# 7segement4digits1badidea-shield-mk-4.net
KiCad netlist of a schematic drawn in EAGLE
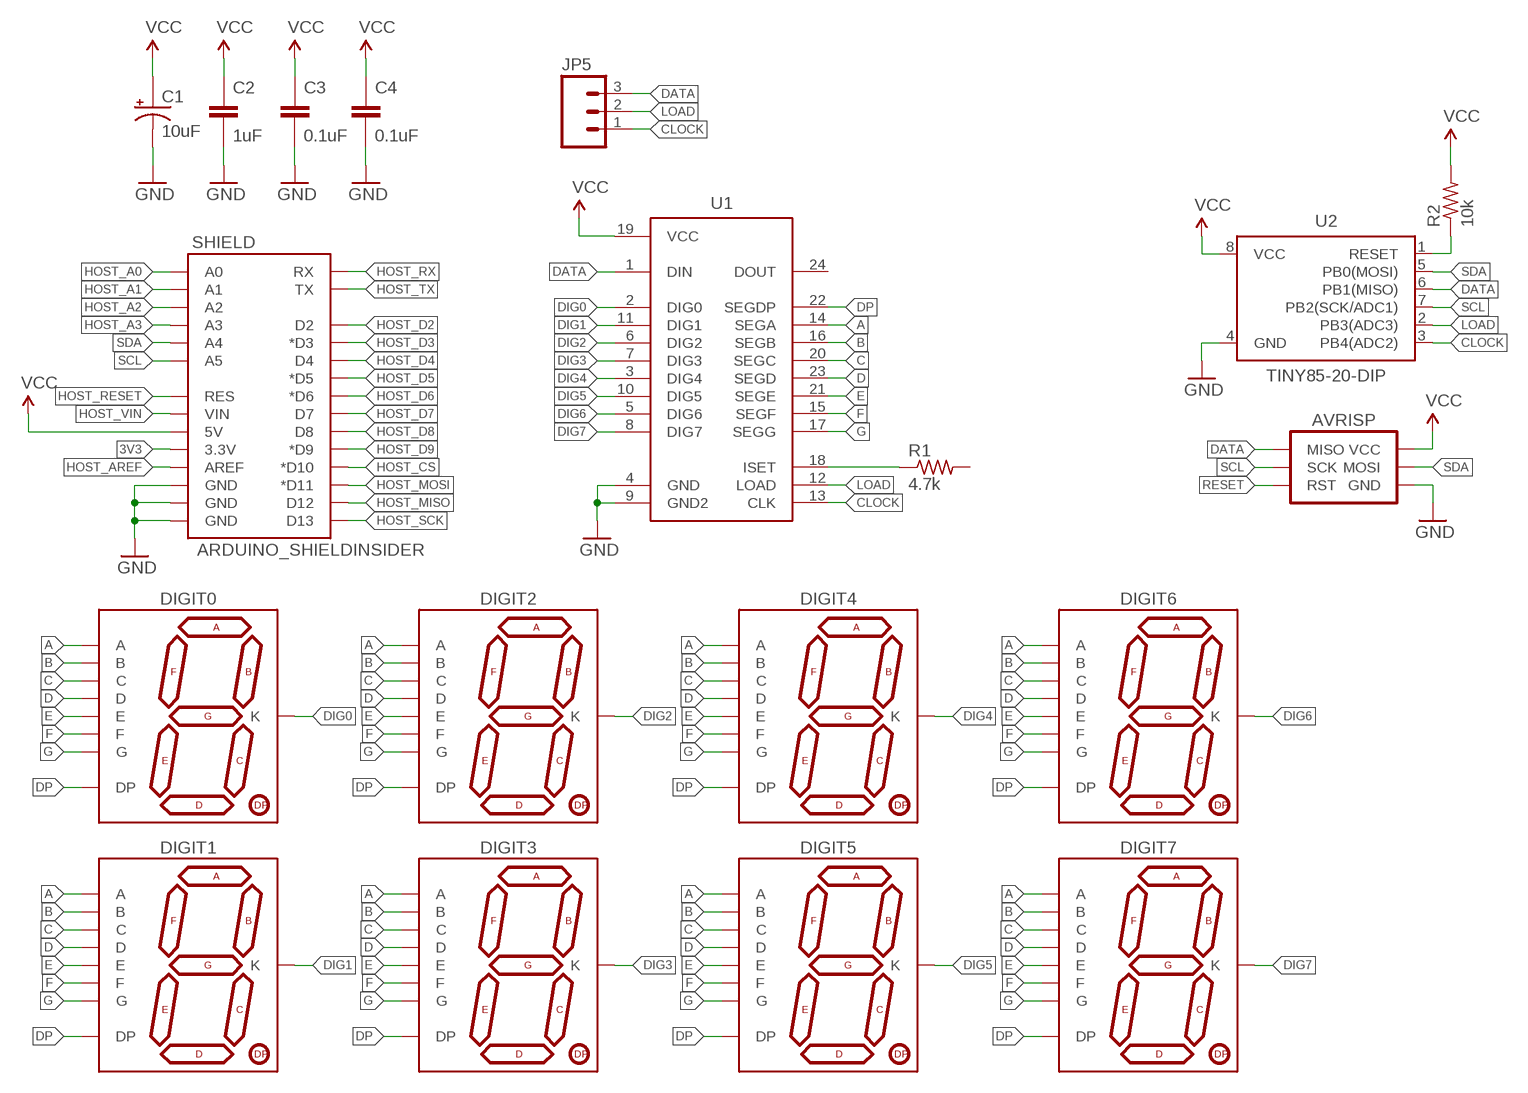
[diagram p0: schematic, sheet 1]

(export (version "E")
  (design (tool "Eeschema 10.0.6"))
  (components
    (comp (ref "AVRISP")
      (value "AVR_SPI_PRG_6PTH")
      (footprint "eagle-import:2X3")
      (libsource (lib "eagle-import") (part "AVR_SPI_PRG_6PTH"))
    )
    (comp (ref "C1")
      (value "10uF")
      (footprint "eagle-import:E2,5-5")
      (libsource (lib "eagle-import") (part "CAPACITOR-POLARIZEDE2.5-5"))
    )
    (comp (ref "C2")
      (value "1uF")
      (footprint "eagle-import:C025-024X044")
      (libsource (lib "eagle-import") (part "CAPACITOR-CERAMIC025-024X044"))
    )
    (comp (ref "C3")
      (value "0.1uF")
      (footprint "eagle-import:C025-024X044")
      (libsource (lib "eagle-import") (part "CAPACITOR-CERAMIC025-024X044"))
    )
    (comp (ref "C4")
      (value "0.1uF")
      (footprint "eagle-import:C025-024X044")
      (libsource (lib "eagle-import") (part "CAPACITOR-CERAMIC025-024X044"))
    )
    (comp (ref "DIGIT0")
      (value "7SEG_1DIGPTH-10MM")
      (footprint "eagle-import:7SEG_1DIG_10MM")
      (libsource (lib "eagle-import") (part "7SEG_1DIGPTH-10MM"))
    )
    (comp (ref "DIGIT1")
      (value "7SEG_1DIGPTH-10MM")
      (footprint "eagle-import:7SEG_1DIG_10MM")
      (libsource (lib "eagle-import") (part "7SEG_1DIGPTH-10MM"))
    )
    (comp (ref "DIGIT2")
      (value "7SEG_1DIGPTH-10MM")
      (footprint "eagle-import:7SEG_1DIG_10MM")
      (libsource (lib "eagle-import") (part "7SEG_1DIGPTH-10MM"))
    )
    (comp (ref "DIGIT3")
      (value "7SEG_1DIGPTH-10MM")
      (footprint "eagle-import:7SEG_1DIG_10MM")
      (libsource (lib "eagle-import") (part "7SEG_1DIGPTH-10MM"))
    )
    (comp (ref "DIGIT4")
      (value "7SEG_1DIGPTH-10MM")
      (footprint "eagle-import:7SEG_1DIG_10MM")
      (libsource (lib "eagle-import") (part "7SEG_1DIGPTH-10MM"))
    )
    (comp (ref "DIGIT5")
      (value "7SEG_1DIGPTH-10MM")
      (footprint "eagle-import:7SEG_1DIG_10MM")
      (libsource (lib "eagle-import") (part "7SEG_1DIGPTH-10MM"))
    )
    (comp (ref "DIGIT6")
      (value "7SEG_1DIGPTH-10MM")
      (footprint "eagle-import:7SEG_1DIG_10MM")
      (libsource (lib "eagle-import") (part "7SEG_1DIGPTH-10MM"))
    )
    (comp (ref "DIGIT7")
      (value "7SEG_1DIGPTH-10MM")
      (footprint "eagle-import:7SEG_1DIG_10MM")
      (libsource (lib "eagle-import") (part "7SEG_1DIGPTH-10MM"))
    )
    (comp (ref "JP5")
      (value "M03PTH")
      (footprint "eagle-import:1X03")
      (libsource (lib "eagle-import") (part "M03PTH"))
    )
    (comp (ref "R1")
      (value "4.7k")
      (footprint "eagle-import:RESISTOR-AXIAL-PTH-7.68MM")
      (libsource (lib "eagle-import") (part "RESISTORPTH-AXIAL-7.68MM"))
    )
    (comp (ref "R2")
      (value "10k")
      (footprint "eagle-import:RESISTOR-AXIAL-PTH-7.68MM")
      (libsource (lib "eagle-import") (part "RESISTORPTH-AXIAL-7.68MM"))
    )
    (comp (ref "SHIELD")
      (value "ARDUINO_SHIELDINSIDER")
      (footprint "eagle-import:ARDUINO_SHIELD_NOOUTLINE_INSIDE")
      (libsource (lib "eagle-import") (part "ARDUINO_SHIELDINSIDER"))
    )
    (comp (ref "U1")
      (value "MAX7219DIP")
      (footprint "eagle-import:DIL24")
      (libsource (lib "eagle-import") (part "MAX7219DIP"))
    )
    (comp (ref "U2")
      (value "TINY85-20-DIP")
      (footprint "eagle-import:DIP08")
      (libsource (lib "eagle-import") (part "ATTINY45TINY85-20-DIP"))
    )
  )
  (nets
    (net (code "1") (name "3V3") (class "Default")
      (node (ref "SHIELD") (pin "3.3V") (pinfunction "3.3V_3.3V") (pintype "bidirectional"))
    )
    (net (code "2") (name "A") (class "Default")
      (node (ref "DIGIT0") (pin "10") (pinfunction "A_10") (pintype "bidirectional"))
      (node (ref "DIGIT1") (pin "10") (pinfunction "A_10") (pintype "bidirectional"))
      (node (ref "DIGIT2") (pin "10") (pinfunction "A_10") (pintype "bidirectional"))
      (node (ref "DIGIT3") (pin "10") (pinfunction "A_10") (pintype "bidirectional"))
      (node (ref "DIGIT4") (pin "10") (pinfunction "A_10") (pintype "bidirectional"))
      (node (ref "DIGIT5") (pin "10") (pinfunction "A_10") (pintype "bidirectional"))
      (node (ref "DIGIT6") (pin "10") (pinfunction "A_10") (pintype "bidirectional"))
      (node (ref "DIGIT7") (pin "10") (pinfunction "A_10") (pintype "bidirectional"))
      (node (ref "U1") (pin "14") (pinfunction "SEGA_14") (pintype "bidirectional"))
    )
    (net (code "3") (name "B") (class "Default")
      (node (ref "DIGIT0") (pin "9") (pinfunction "B_9") (pintype "bidirectional"))
      (node (ref "DIGIT1") (pin "9") (pinfunction "B_9") (pintype "bidirectional"))
      (node (ref "DIGIT2") (pin "9") (pinfunction "B_9") (pintype "bidirectional"))
      (node (ref "DIGIT3") (pin "9") (pinfunction "B_9") (pintype "bidirectional"))
      (node (ref "DIGIT4") (pin "9") (pinfunction "B_9") (pintype "bidirectional"))
      (node (ref "DIGIT5") (pin "9") (pinfunction "B_9") (pintype "bidirectional"))
      (node (ref "DIGIT6") (pin "9") (pinfunction "B_9") (pintype "bidirectional"))
      (node (ref "DIGIT7") (pin "9") (pinfunction "B_9") (pintype "bidirectional"))
      (node (ref "U1") (pin "16") (pinfunction "SEGB_16") (pintype "bidirectional"))
    )
    (net (code "4") (name "C") (class "Default")
      (node (ref "DIGIT0") (pin "8") (pinfunction "C_8") (pintype "bidirectional"))
      (node (ref "DIGIT1") (pin "8") (pinfunction "C_8") (pintype "bidirectional"))
      (node (ref "DIGIT2") (pin "8") (pinfunction "C_8") (pintype "bidirectional"))
      (node (ref "DIGIT3") (pin "8") (pinfunction "C_8") (pintype "bidirectional"))
      (node (ref "DIGIT4") (pin "8") (pinfunction "C_8") (pintype "bidirectional"))
      (node (ref "DIGIT5") (pin "8") (pinfunction "C_8") (pintype "bidirectional"))
      (node (ref "DIGIT6") (pin "8") (pinfunction "C_8") (pintype "bidirectional"))
      (node (ref "DIGIT7") (pin "8") (pinfunction "C_8") (pintype "bidirectional"))
      (node (ref "U1") (pin "20") (pinfunction "SEGC_20") (pintype "bidirectional"))
    )
    (net (code "5") (name "CLOCK") (class "Default")
      (node (ref "JP5") (pin "1") (pinfunction "1_1") (pintype "passive"))
      (node (ref "U1") (pin "13") (pinfunction "CLK_13") (pintype "bidirectional"))
      (node (ref "U2") (pin "3") (pinfunction "PB4(ADC2)_3") (pintype "bidirectional"))
    )
    (net (code "6") (name "D") (class "Default")
      (node (ref "DIGIT0") (pin "5") (pinfunction "D_5") (pintype "bidirectional"))
      (node (ref "DIGIT1") (pin "5") (pinfunction "D_5") (pintype "bidirectional"))
      (node (ref "DIGIT2") (pin "5") (pinfunction "D_5") (pintype "bidirectional"))
      (node (ref "DIGIT3") (pin "5") (pinfunction "D_5") (pintype "bidirectional"))
      (node (ref "DIGIT4") (pin "5") (pinfunction "D_5") (pintype "bidirectional"))
      (node (ref "DIGIT5") (pin "5") (pinfunction "D_5") (pintype "bidirectional"))
      (node (ref "DIGIT6") (pin "5") (pinfunction "D_5") (pintype "bidirectional"))
      (node (ref "DIGIT7") (pin "5") (pinfunction "D_5") (pintype "bidirectional"))
      (node (ref "U1") (pin "23") (pinfunction "SEGD_23") (pintype "bidirectional"))
    )
    (net (code "7") (name "DATA") (class "Default")
      (node (ref "AVRISP") (pin "1") (pinfunction "MISO_1") (pintype "passive"))
      (node (ref "JP5") (pin "3") (pinfunction "3_3") (pintype "passive"))
      (node (ref "U1") (pin "1") (pinfunction "DIN_1") (pintype "bidirectional"))
      (node (ref "U2") (pin "6") (pinfunction "PB1(MISO)_6") (pintype "bidirectional"))
    )
    (net (code "8") (name "DIG0") (class "Default")
      (node (ref "DIGIT0") (pin "1") (pinfunction "K_1") (pintype "bidirectional"))
      (node (ref "DIGIT0") (pin "6") (pinfunction "K_6") (pintype "bidirectional"))
      (node (ref "U1") (pin "2") (pinfunction "DIG0_2") (pintype "bidirectional"))
    )
    (net (code "9") (name "DIG1") (class "Default")
      (node (ref "DIGIT1") (pin "1") (pinfunction "K_1") (pintype "bidirectional"))
      (node (ref "DIGIT1") (pin "6") (pinfunction "K_6") (pintype "bidirectional"))
      (node (ref "U1") (pin "11") (pinfunction "DIG1_11") (pintype "bidirectional"))
    )
    (net (code "10") (name "DIG2") (class "Default")
      (node (ref "DIGIT2") (pin "1") (pinfunction "K_1") (pintype "bidirectional"))
      (node (ref "DIGIT2") (pin "6") (pinfunction "K_6") (pintype "bidirectional"))
      (node (ref "U1") (pin "6") (pinfunction "DIG2_6") (pintype "bidirectional"))
    )
    (net (code "11") (name "DIG3") (class "Default")
      (node (ref "DIGIT3") (pin "1") (pinfunction "K_1") (pintype "bidirectional"))
      (node (ref "DIGIT3") (pin "6") (pinfunction "K_6") (pintype "bidirectional"))
      (node (ref "U1") (pin "7") (pinfunction "DIG3_7") (pintype "bidirectional"))
    )
    (net (code "12") (name "DIG4") (class "Default")
      (node (ref "DIGIT4") (pin "1") (pinfunction "K_1") (pintype "bidirectional"))
      (node (ref "DIGIT4") (pin "6") (pinfunction "K_6") (pintype "bidirectional"))
      (node (ref "U1") (pin "3") (pinfunction "DIG4_3") (pintype "bidirectional"))
    )
    (net (code "13") (name "DIG5") (class "Default")
      (node (ref "DIGIT5") (pin "1") (pinfunction "K_1") (pintype "bidirectional"))
      (node (ref "DIGIT5") (pin "6") (pinfunction "K_6") (pintype "bidirectional"))
      (node (ref "U1") (pin "10") (pinfunction "DIG5_10") (pintype "bidirectional"))
    )
    (net (code "14") (name "DIG6") (class "Default")
      (node (ref "DIGIT6") (pin "1") (pinfunction "K_1") (pintype "bidirectional"))
      (node (ref "DIGIT6") (pin "6") (pinfunction "K_6") (pintype "bidirectional"))
      (node (ref "U1") (pin "5") (pinfunction "DIG6_5") (pintype "bidirectional"))
    )
    (net (code "15") (name "DIG7") (class "Default")
      (node (ref "DIGIT7") (pin "1") (pinfunction "K_1") (pintype "bidirectional"))
      (node (ref "DIGIT7") (pin "6") (pinfunction "K_6") (pintype "bidirectional"))
      (node (ref "U1") (pin "8") (pinfunction "DIG7_8") (pintype "bidirectional"))
    )
    (net (code "16") (name "DP") (class "Default")
      (node (ref "DIGIT0") (pin "7") (pinfunction "DP_7") (pintype "bidirectional"))
      (node (ref "DIGIT1") (pin "7") (pinfunction "DP_7") (pintype "bidirectional"))
      (node (ref "DIGIT2") (pin "7") (pinfunction "DP_7") (pintype "bidirectional"))
      (node (ref "DIGIT3") (pin "7") (pinfunction "DP_7") (pintype "bidirectional"))
      (node (ref "DIGIT4") (pin "7") (pinfunction "DP_7") (pintype "bidirectional"))
      (node (ref "DIGIT5") (pin "7") (pinfunction "DP_7") (pintype "bidirectional"))
      (node (ref "DIGIT6") (pin "7") (pinfunction "DP_7") (pintype "bidirectional"))
      (node (ref "DIGIT7") (pin "7") (pinfunction "DP_7") (pintype "bidirectional"))
      (node (ref "U1") (pin "22") (pinfunction "SEGDP_22") (pintype "bidirectional"))
    )
    (net (code "17") (name "E") (class "Default")
      (node (ref "DIGIT0") (pin "4") (pinfunction "E_4") (pintype "bidirectional"))
      (node (ref "DIGIT1") (pin "4") (pinfunction "E_4") (pintype "bidirectional"))
      (node (ref "DIGIT2") (pin "4") (pinfunction "E_4") (pintype "bidirectional"))
      (node (ref "DIGIT3") (pin "4") (pinfunction "E_4") (pintype "bidirectional"))
      (node (ref "DIGIT4") (pin "4") (pinfunction "E_4") (pintype "bidirectional"))
      (node (ref "DIGIT5") (pin "4") (pinfunction "E_4") (pintype "bidirectional"))
      (node (ref "DIGIT6") (pin "4") (pinfunction "E_4") (pintype "bidirectional"))
      (node (ref "DIGIT7") (pin "4") (pinfunction "E_4") (pintype "bidirectional"))
      (node (ref "U1") (pin "21") (pinfunction "SEGE_21") (pintype "bidirectional"))
    )
    (net (code "18") (name "F") (class "Default")
      (node (ref "DIGIT0") (pin "2") (pinfunction "F_2") (pintype "bidirectional"))
      (node (ref "DIGIT1") (pin "2") (pinfunction "F_2") (pintype "bidirectional"))
      (node (ref "DIGIT2") (pin "2") (pinfunction "F_2") (pintype "bidirectional"))
      (node (ref "DIGIT3") (pin "2") (pinfunction "F_2") (pintype "bidirectional"))
      (node (ref "DIGIT4") (pin "2") (pinfunction "F_2") (pintype "bidirectional"))
      (node (ref "DIGIT5") (pin "2") (pinfunction "F_2") (pintype "bidirectional"))
      (node (ref "DIGIT6") (pin "2") (pinfunction "F_2") (pintype "bidirectional"))
      (node (ref "DIGIT7") (pin "2") (pinfunction "F_2") (pintype "bidirectional"))
      (node (ref "U1") (pin "15") (pinfunction "SEGF_15") (pintype "bidirectional"))
    )
    (net (code "19") (name "G") (class "Default")
      (node (ref "DIGIT0") (pin "3") (pinfunction "G_3") (pintype "bidirectional"))
      (node (ref "DIGIT1") (pin "3") (pinfunction "G_3") (pintype "bidirectional"))
      (node (ref "DIGIT2") (pin "3") (pinfunction "G_3") (pintype "bidirectional"))
      (node (ref "DIGIT3") (pin "3") (pinfunction "G_3") (pintype "bidirectional"))
      (node (ref "DIGIT4") (pin "3") (pinfunction "G_3") (pintype "bidirectional"))
      (node (ref "DIGIT5") (pin "3") (pinfunction "G_3") (pintype "bidirectional"))
      (node (ref "DIGIT6") (pin "3") (pinfunction "G_3") (pintype "bidirectional"))
      (node (ref "DIGIT7") (pin "3") (pinfunction "G_3") (pintype "bidirectional"))
      (node (ref "U1") (pin "17") (pinfunction "SEGG_17") (pintype "bidirectional"))
    )
    (net (code "20") (name "GND") (class "Default")
      (node (ref "AVRISP") (pin "6") (pinfunction "GND_6") (pintype "passive"))
      (node (ref "C1") (pin "-") (pinfunction "-_-") (pintype "passive"))
      (node (ref "C2") (pin "2") (pinfunction "2_2") (pintype "passive"))
      (node (ref "C3") (pin "2") (pinfunction "2_2") (pintype "passive"))
      (node (ref "C4") (pin "2") (pinfunction "2_2") (pintype "passive"))
      (node (ref "SHIELD") (pin "GND@0") (pinfunction "GND_GND@0") (pintype "bidirectional"))
      (node (ref "SHIELD") (pin "GND@1") (pinfunction "GND_GND@1") (pintype "bidirectional"))
      (node (ref "SHIELD") (pin "GND@2") (pinfunction "GND_GND@2") (pintype "bidirectional"))
      (node (ref "U1") (pin "4") (pinfunction "GND_4") (pintype "bidirectional"))
      (node (ref "U1") (pin "9") (pinfunction "GND2_9") (pintype "bidirectional"))
      (node (ref "U2") (pin "4") (pinfunction "GND_4") (pintype "bidirectional"))
    )
    (net (code "21") (name "HOST_A0") (class "Default")
      (node (ref "SHIELD") (pin "A0") (pinfunction "A0_A0") (pintype "bidirectional"))
    )
    (net (code "22") (name "HOST_A1") (class "Default")
      (node (ref "SHIELD") (pin "A1") (pinfunction "A1_A1") (pintype "bidirectional"))
    )
    (net (code "23") (name "HOST_A2") (class "Default")
      (node (ref "SHIELD") (pin "A2") (pinfunction "A2_A2") (pintype "bidirectional"))
    )
    (net (code "24") (name "HOST_A3") (class "Default")
      (node (ref "SHIELD") (pin "A3") (pinfunction "A3_A3") (pintype "bidirectional"))
    )
    (net (code "25") (name "HOST_AREF") (class "Default")
      (node (ref "SHIELD") (pin "AREF") (pinfunction "AREF_AREF") (pintype "bidirectional"))
    )
    (net (code "26") (name "HOST_CS") (class "Default")
      (node (ref "SHIELD") (pin "D10") (pinfunction "*D10_D10") (pintype "bidirectional"))
    )
    (net (code "27") (name "HOST_D2") (class "Default")
      (node (ref "SHIELD") (pin "D2") (pinfunction "D2_D2") (pintype "bidirectional"))
    )
    (net (code "28") (name "HOST_D3") (class "Default")
      (node (ref "SHIELD") (pin "D3") (pinfunction "*D3_D3") (pintype "bidirectional"))
    )
    (net (code "29") (name "HOST_D4") (class "Default")
      (node (ref "SHIELD") (pin "D4") (pinfunction "D4_D4") (pintype "bidirectional"))
    )
    (net (code "30") (name "HOST_D5") (class "Default")
      (node (ref "SHIELD") (pin "D5") (pinfunction "*D5_D5") (pintype "bidirectional"))
    )
    (net (code "31") (name "HOST_D6") (class "Default")
      (node (ref "SHIELD") (pin "D6") (pinfunction "*D6_D6") (pintype "bidirectional"))
    )
    (net (code "32") (name "HOST_D7") (class "Default")
      (node (ref "SHIELD") (pin "D7") (pinfunction "D7_D7") (pintype "bidirectional"))
    )
    (net (code "33") (name "HOST_D8") (class "Default")
      (node (ref "SHIELD") (pin "D8") (pinfunction "D8_D8") (pintype "bidirectional"))
    )
    (net (code "34") (name "HOST_D9") (class "Default")
      (node (ref "SHIELD") (pin "D9") (pinfunction "*D9_D9") (pintype "bidirectional"))
    )
    (net (code "35") (name "HOST_MISO") (class "Default")
      (node (ref "SHIELD") (pin "D12") (pinfunction "D12_D12") (pintype "bidirectional"))
    )
    (net (code "36") (name "HOST_MOSI") (class "Default")
      (node (ref "SHIELD") (pin "D11") (pinfunction "*D11_D11") (pintype "bidirectional"))
    )
    (net (code "37") (name "HOST_RESET") (class "Default")
      (node (ref "SHIELD") (pin "RES") (pinfunction "RES_RES") (pintype "bidirectional"))
    )
    (net (code "38") (name "HOST_RX") (class "Default")
      (node (ref "SHIELD") (pin "RX") (pinfunction "RX_RX") (pintype "bidirectional"))
    )
    (net (code "39") (name "HOST_SCK") (class "Default")
      (node (ref "SHIELD") (pin "D13") (pinfunction "D13_D13") (pintype "bidirectional"))
    )
    (net (code "40") (name "HOST_TX") (class "Default")
      (node (ref "SHIELD") (pin "TX") (pinfunction "TX_TX") (pintype "bidirectional"))
    )
    (net (code "41") (name "HOST_VIN") (class "Default")
      (node (ref "SHIELD") (pin "VIN") (pinfunction "VIN_VIN") (pintype "bidirectional"))
    )
    (net (code "42") (name "LOAD") (class "Default")
      (node (ref "JP5") (pin "2") (pinfunction "2_2") (pintype "passive"))
      (node (ref "U1") (pin "12") (pinfunction "LOAD_12") (pintype "bidirectional"))
      (node (ref "U2") (pin "2") (pinfunction "PB3(ADC3)_2") (pintype "bidirectional"))
    )
    (net (code "43") (name "Net-(R1-1)") (class "Default")
      (node (ref "R1") (pin "P$1") (pinfunction "1_P$1") (pintype "passive"))
      (node (ref "U1") (pin "18") (pinfunction "ISET_18") (pintype "bidirectional"))
    )
    (net (code "44") (name "Net-(R2-1)") (class "Default")
      (node (ref "R2") (pin "P$1") (pinfunction "1_P$1") (pintype "passive"))
      (node (ref "U2") (pin "1") (pinfunction "RESET_1") (pintype "bidirectional"))
    )
    (net (code "45") (name "RESET") (class "Default")
      (node (ref "AVRISP") (pin "5") (pinfunction "RST_5") (pintype "passive"))
    )
    (net (code "46") (name "SCL") (class "Default")
      (node (ref "AVRISP") (pin "3") (pinfunction "SCK_3") (pintype "passive"))
      (node (ref "SHIELD") (pin "A5") (pinfunction "A5_A5") (pintype "bidirectional"))
      (node (ref "U2") (pin "7") (pinfunction "PB2(SCK/ADC1)_7") (pintype "bidirectional"))
    )
    (net (code "47") (name "SDA") (class "Default")
      (node (ref "AVRISP") (pin "4") (pinfunction "MOSI_4") (pintype "passive"))
      (node (ref "SHIELD") (pin "A4") (pinfunction "A4_A4") (pintype "bidirectional"))
      (node (ref "U2") (pin "5") (pinfunction "PB0(MOSI)_5") (pintype "bidirectional"))
    )
    (net (code "48") (name "VCC") (class "Default")
      (node (ref "AVRISP") (pin "2") (pinfunction "VCC_2") (pintype "passive"))
      (node (ref "C1") (pin "+") (pinfunction "+_+") (pintype "passive"))
      (node (ref "C2") (pin "1") (pinfunction "1_1") (pintype "passive"))
      (node (ref "C3") (pin "1") (pinfunction "1_1") (pintype "passive"))
      (node (ref "C4") (pin "1") (pinfunction "1_1") (pintype "passive"))
      (node (ref "R2") (pin "P$2") (pinfunction "2_P$2") (pintype "passive"))
      (node (ref "SHIELD") (pin "5V") (pinfunction "5V_5V") (pintype "bidirectional"))
      (node (ref "U1") (pin "19") (pinfunction "VCC_19") (pintype "bidirectional"))
      (node (ref "U2") (pin "8") (pinfunction "VCC_8") (pintype "bidirectional"))
    )
    (net (code "49") (name "unconnected-(R1-2-PadP$2)") (class "Default")
      (node (ref "R1") (pin "P$2") (pinfunction "2_P$2") (pintype "passive"))
    )
    (net (code "50") (name "unconnected-(U1-DOUT-Pad24)") (class "Default")
      (node (ref "U1") (pin "24") (pinfunction "DOUT_24") (pintype "bidirectional"))
    )
  )
)
